# ModuleTester.net
KiCad netlist of a schematic drawn in EAGLE
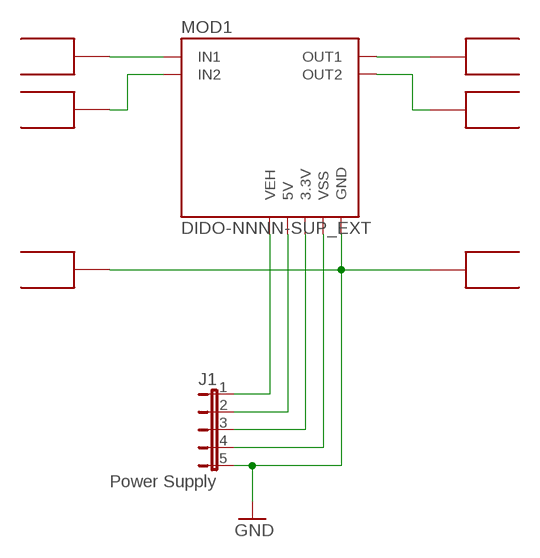
[diagram p0: schematic, sheet 1]

(export (version "E")
  (design (tool "Eeschema 10.0.6"))
  (components
    (comp (ref "J1")
      (value "Power Supply")
      (footprint "eagle-import:JP5")
      (libsource (lib "eagle-import") (part "JP5E"))
    )
    (comp (ref "MOD1")
      (value "DIDO-NNNN-SUP_EXT")
      (footprint "eagle-import:DIDO-NNNN-SUP_EXT")
      (libsource (lib "eagle-import") (part "DIDO-NNNN-SUP_EXT"))
    )
    (comp (ref "U$1")
      (value "BANANA-PLUGROUND")
      (footprint "eagle-import:6MM-PAD-ROUND")
      (libsource (lib "eagle-import") (part "BANANA-PLUGROUND"))
    )
    (comp (ref "U$2")
      (value "BANANA-PLUGROUND")
      (footprint "eagle-import:6MM-PAD-ROUND")
      (libsource (lib "eagle-import") (part "BANANA-PLUGROUND"))
    )
    (comp (ref "U$3")
      (value "BANANA-PLUGROUND")
      (footprint "eagle-import:6MM-PAD-ROUND")
      (libsource (lib "eagle-import") (part "BANANA-PLUGROUND"))
    )
    (comp (ref "U$4")
      (value "BANANA-PLUGROUND")
      (footprint "eagle-import:6MM-PAD-ROUND")
      (libsource (lib "eagle-import") (part "BANANA-PLUGROUND"))
    )
    (comp (ref "U$5")
      (value "BANANA-PLUGROUND")
      (footprint "eagle-import:6MM-PAD-ROUND")
      (libsource (lib "eagle-import") (part "BANANA-PLUGROUND"))
    )
    (comp (ref "U$6")
      (value "BANANA-PLUGROUND")
      (footprint "eagle-import:6MM-PAD-ROUND")
      (libsource (lib "eagle-import") (part "BANANA-PLUGROUND"))
    )
  )
  (nets
    (net (code "1") (name "GND") (class "Default")
      (node (ref "J1") (pin "5") (pinfunction "5_5") (pintype "passive"))
      (node (ref "MOD1") (pin "GND1") (pinfunction "GND_GND1") (pintype "power_in"))
      (node (ref "MOD1") (pin "GND2") (pinfunction "GND_GND2") (pintype "power_in"))
      (node (ref "MOD1") (pin "GND3") (pinfunction "GND_GND3") (pintype "power_in"))
      (node (ref "MOD1") (pin "GND4") (pinfunction "GND_GND4") (pintype "power_in"))
      (node (ref "U$5") (pin "1") (pinfunction "P$1_1") (pintype "bidirectional"))
      (node (ref "U$6") (pin "1") (pinfunction "P$1_1") (pintype "bidirectional"))
    )
    (net (code "2") (name "Net-(J1-Pad1)") (class "Default")
      (node (ref "J1") (pin "1") (pinfunction "1_1") (pintype "passive"))
      (node (ref "MOD1") (pin "VEH") (pinfunction "VEH_VEH") (pintype "power_in"))
    )
    (net (code "3") (name "Net-(J1-Pad2)") (class "Default")
      (node (ref "J1") (pin "2") (pinfunction "2_2") (pintype "passive"))
      (node (ref "MOD1") (pin "5V") (pinfunction "5V_5V") (pintype "power_in"))
    )
    (net (code "4") (name "Net-(J1-Pad3)") (class "Default")
      (node (ref "J1") (pin "3") (pinfunction "3_3") (pintype "passive"))
      (node (ref "MOD1") (pin "3.3V") (pinfunction "3.3V_3.3V") (pintype "power_in"))
    )
    (net (code "5") (name "Net-(J1-Pad4)") (class "Default")
      (node (ref "J1") (pin "4") (pinfunction "4_4") (pintype "passive"))
      (node (ref "MOD1") (pin "VSS") (pinfunction "VSS_VSS") (pintype "power_in"))
    )
    (net (code "6") (name "Net-(U$1-P$1)") (class "Default")
      (node (ref "MOD1") (pin "OUT1") (pinfunction "OUT1_OUT1") (pintype "output"))
      (node (ref "MOD1") (pin "OUT2") (pinfunction "OUT1_OUT2") (pintype "output"))
      (node (ref "MOD1") (pin "OUT3") (pinfunction "OUT1_OUT3") (pintype "output"))
      (node (ref "MOD1") (pin "OUT4") (pinfunction "OUT1_OUT4") (pintype "output"))
      (node (ref "U$1") (pin "1") (pinfunction "P$1_1") (pintype "bidirectional"))
    )
    (net (code "7") (name "Net-(U$2-P$1)") (class "Default")
      (node (ref "MOD1") (pin "OUT2_1") (pinfunction "OUT2_OUT2_1") (pintype "output"))
      (node (ref "MOD1") (pin "OUT2_2") (pinfunction "OUT2_OUT2_2") (pintype "output"))
      (node (ref "MOD1") (pin "OUT2_3") (pinfunction "OUT2_OUT2_3") (pintype "output"))
      (node (ref "MOD1") (pin "OUT2_4") (pinfunction "OUT2_OUT2_4") (pintype "output"))
      (node (ref "U$2") (pin "1") (pinfunction "P$1_1") (pintype "bidirectional"))
    )
    (net (code "8") (name "Net-(U$3-P$1)") (class "Default")
      (node (ref "MOD1") (pin "IN1") (pinfunction "IN1_IN1") (pintype "input"))
      (node (ref "MOD1") (pin "IN2") (pinfunction "IN1_IN2") (pintype "input"))
      (node (ref "MOD1") (pin "IN3") (pinfunction "IN1_IN3") (pintype "input"))
      (node (ref "MOD1") (pin "IN4") (pinfunction "IN1_IN4") (pintype "input"))
      (node (ref "U$3") (pin "1") (pinfunction "P$1_1") (pintype "bidirectional"))
    )
    (net (code "9") (name "Net-(U$4-P$1)") (class "Default")
      (node (ref "MOD1") (pin "IN2_1") (pinfunction "IN2_IN2_1") (pintype "input"))
      (node (ref "MOD1") (pin "IN2_2") (pinfunction "IN2_IN2_2") (pintype "input"))
      (node (ref "MOD1") (pin "IN2_3") (pinfunction "IN2_IN2_3") (pintype "input"))
      (node (ref "MOD1") (pin "IN2_4") (pinfunction "IN2_IN2_4") (pintype "input"))
      (node (ref "U$4") (pin "1") (pinfunction "P$1_1") (pintype "bidirectional"))
    )
  )
)
